# sleep-monitor.net
KiCad netlist of a schematic drawn in EasyEDA Pro
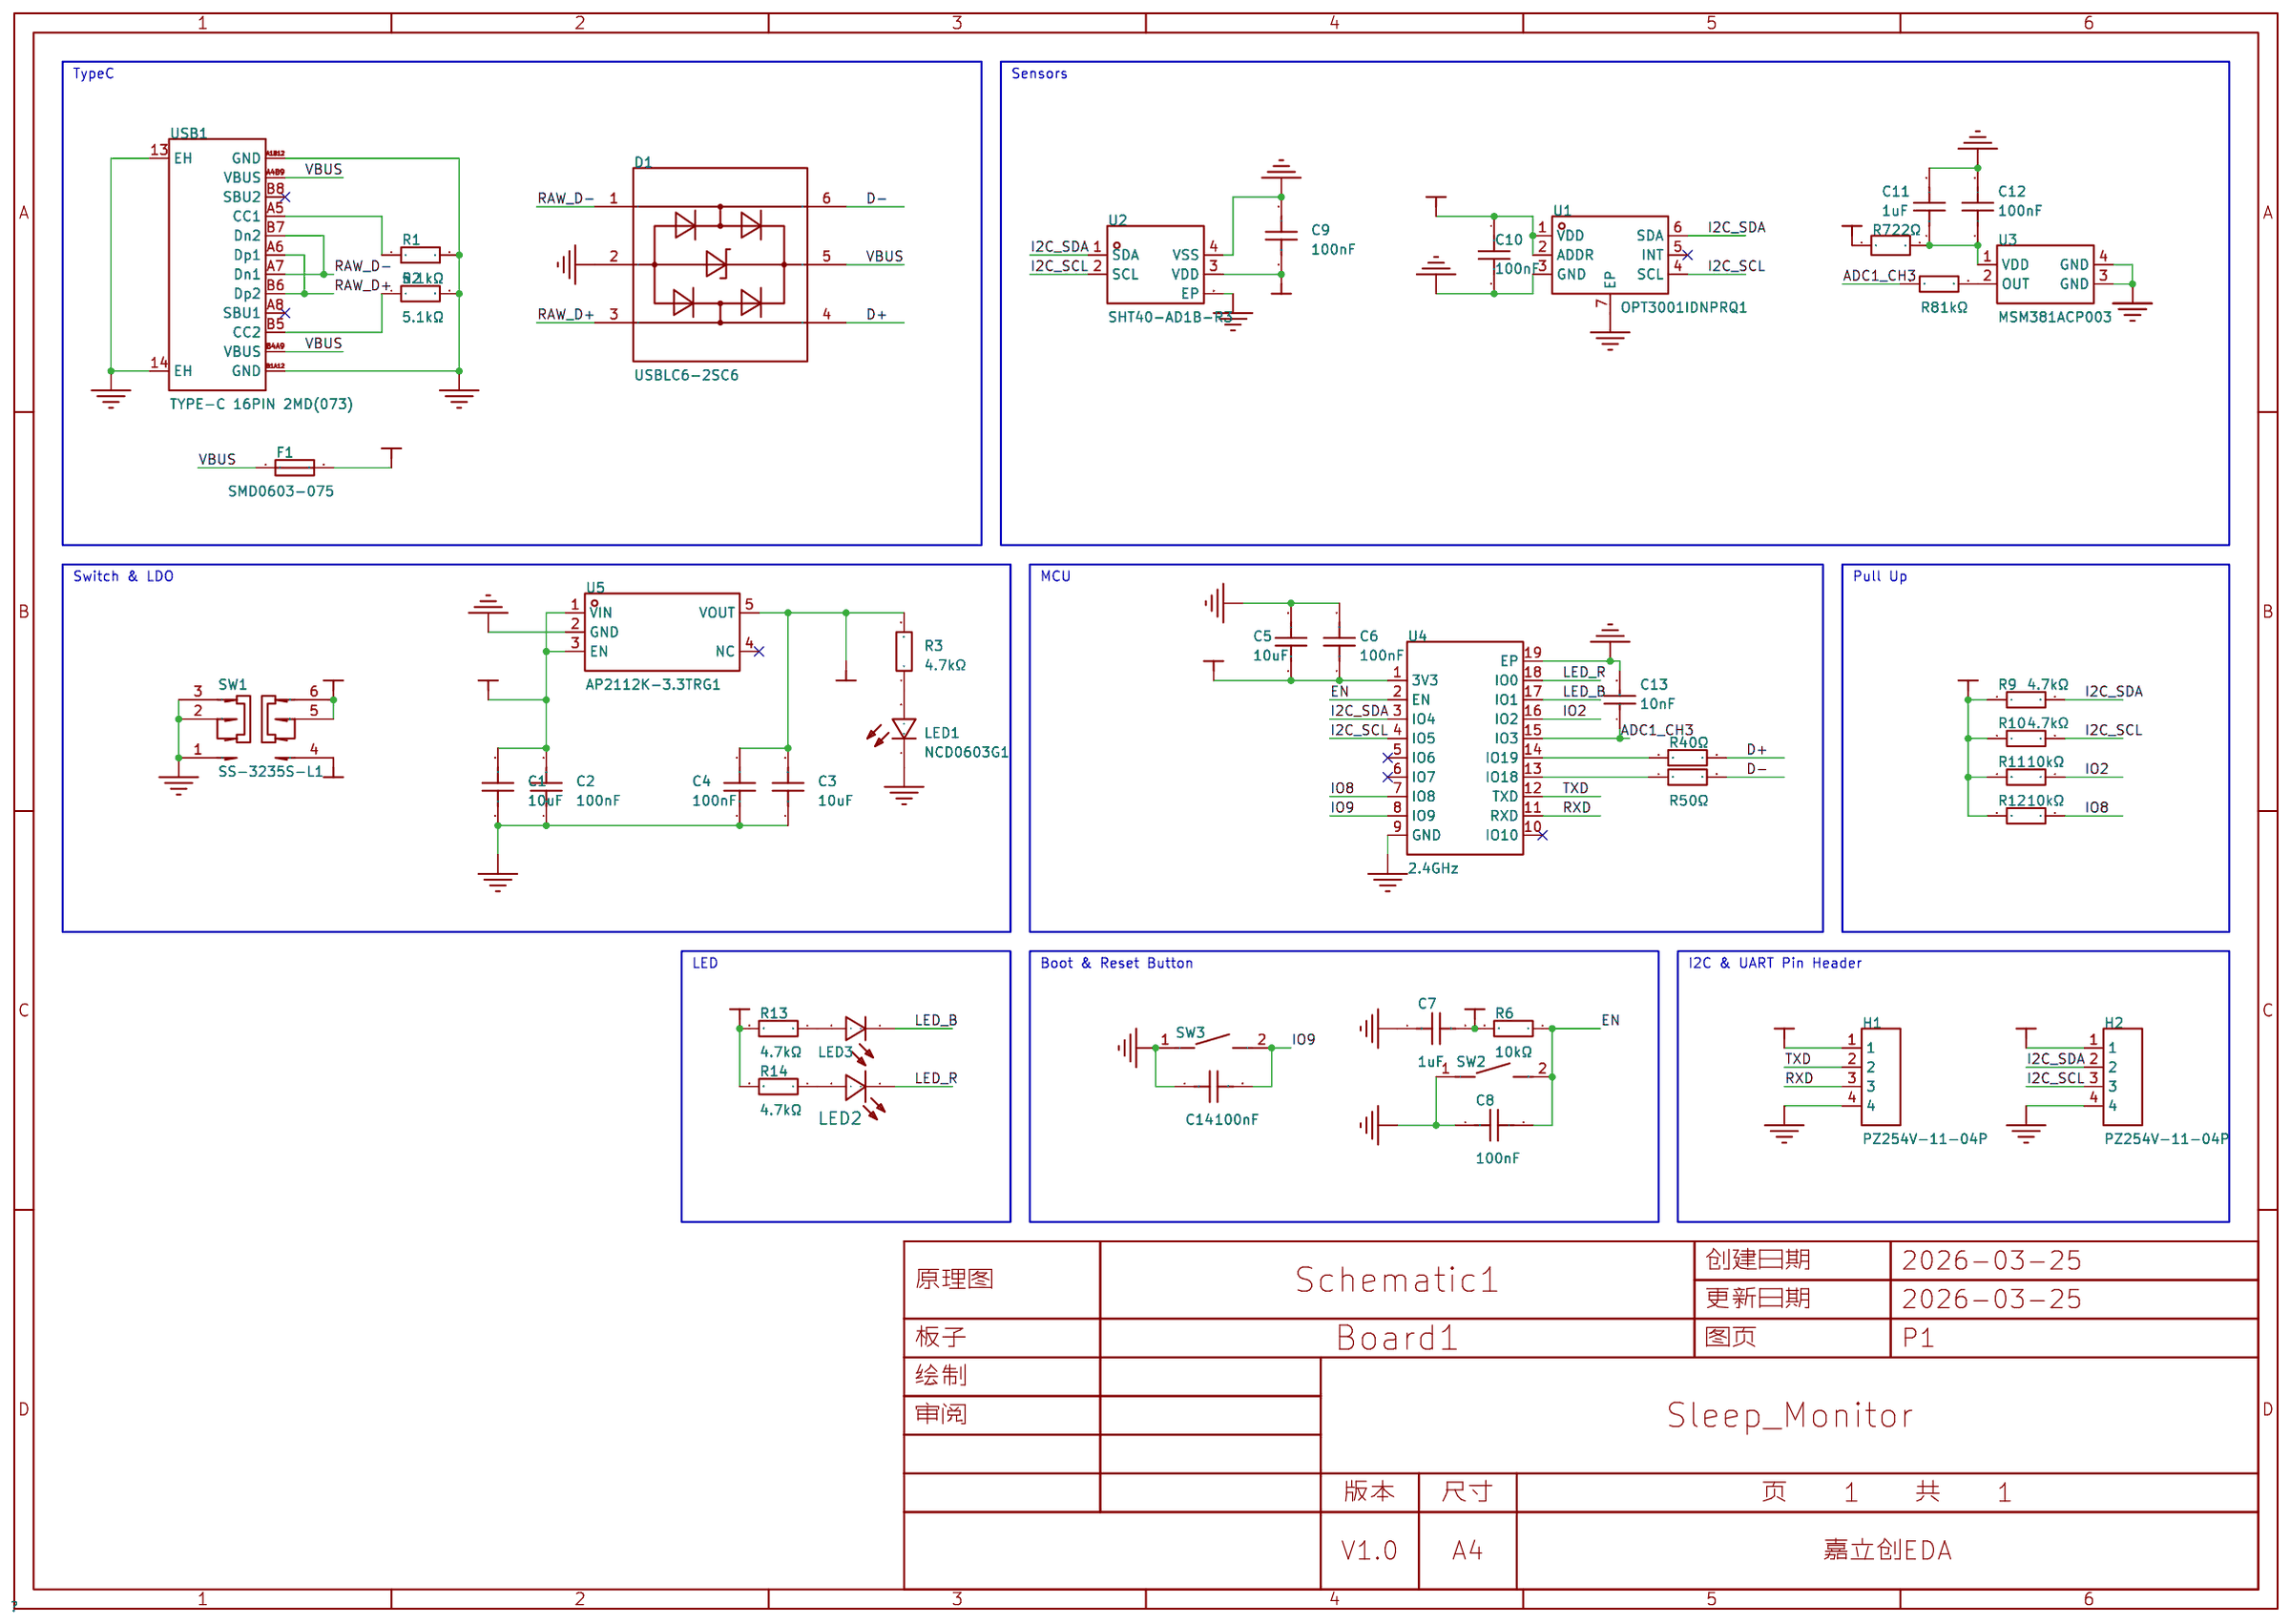
[diagram p0: schematic sheet]

(export (version "E")
  (design (tool "Eeschema 10.0.6"))
  (components
    (comp (ref "C1")
      (value "10uF")
      (footprint "easyedapro:C0603")
      (description "容值:10uF;精度:±10%;额定电压:10V;温度系数:X5R;")
      (fields
        (field (name "Manufacturer Part") "CL10A106KP8NNNC")
        (field (name "Manufacturer") "SAMSUNG(三星)")
      )
      (libsource (lib "easyedapro") (part "CL10A106KP8NNNC"))
    )
    (comp (ref "C2")
      (value "100nF")
      (footprint "easyedapro:C0603")
      (description "容值:100nF;精度:±10%;额定电压:50V;温度系数:X7R;")
      (fields
        (field (name "Manufacturer Part") "CL10B104KB8NNNC")
        (field (name "Manufacturer") "SAMSUNG(三星)")
      )
      (libsource (lib "easyedapro") (part "CL10B104KB8NNNC"))
    )
    (comp (ref "C3")
      (value "10uF")
      (footprint "easyedapro:C0603")
      (description "容值:10uF;精度:±10%;额定电压:10V;温度系数:X5R;")
      (fields
        (field (name "Manufacturer Part") "CL10A106KP8NNNC")
        (field (name "Manufacturer") "SAMSUNG(三星)")
      )
      (libsource (lib "easyedapro") (part "CL10A106KP8NNNC"))
    )
    (comp (ref "C4")
      (value "100nF")
      (footprint "easyedapro:C0603")
      (description "容值:100nF;精度:±10%;额定电压:50V;温度系数:X7R;")
      (fields
        (field (name "Manufacturer Part") "CL10B104KB8NNNC")
        (field (name "Manufacturer") "SAMSUNG(三星)")
      )
      (libsource (lib "easyedapro") (part "CL10B104KB8NNNC"))
    )
    (comp (ref "C5")
      (value "10uF")
      (footprint "easyedapro:C0603")
      (description "容值:10uF;精度:±10%;额定电压:10V;温度系数:X5R;")
      (fields
        (field (name "Manufacturer Part") "CL10A106KP8NNNC")
        (field (name "Manufacturer") "SAMSUNG(三星)")
      )
      (libsource (lib "easyedapro") (part "CL10A106KP8NNNC"))
    )
    (comp (ref "C6")
      (value "100nF")
      (footprint "easyedapro:C0603")
      (description "容值:100nF;精度:±10%;额定电压:50V;温度系数:X7R;")
      (fields
        (field (name "Manufacturer Part") "CL10B104KB8NNNC")
        (field (name "Manufacturer") "SAMSUNG(三星)")
      )
      (libsource (lib "easyedapro") (part "CL10B104KB8NNNC"))
    )
    (comp (ref "C7")
      (value "1uF")
      (footprint "easyedapro:C0603")
      (description "容值:1uF;精度:±10%;额定电压:50V;温度系数:X5R;")
      (fields
        (field (name "Manufacturer Part") "CL10A105KB8NNNC")
        (field (name "Manufacturer") "SAMSUNG(三星)")
      )
      (libsource (lib "easyedapro") (part "CL10A105KB8NNNC"))
    )
    (comp (ref "C8")
      (value "100nF")
      (footprint "easyedapro:C0603")
      (description "容值:100nF;精度:±10%;额定电压:50V;温度系数:X7R;")
      (fields
        (field (name "Manufacturer Part") "CL10B104KB8NNNC")
        (field (name "Manufacturer") "SAMSUNG(三星)")
      )
      (libsource (lib "easyedapro") (part "CL10B104KB8NNNC"))
    )
    (comp (ref "C9")
      (value "100nF")
      (footprint "easyedapro:C0603")
      (description "容值:100nF;精度:±10%;额定电压:50V;温度系数:X7R;")
      (fields
        (field (name "Manufacturer Part") "CL10B104KB8NNNC")
        (field (name "Manufacturer") "SAMSUNG(三星)")
      )
      (libsource (lib "easyedapro") (part "CL10B104KB8NNNC"))
    )
    (comp (ref "C10")
      (value "100nF")
      (footprint "easyedapro:C0603")
      (description "容值:100nF;精度:±10%;额定电压:50V;温度系数:X7R;")
      (fields
        (field (name "Manufacturer Part") "CL10B104KB8NNNC")
        (field (name "Manufacturer") "SAMSUNG(三星)")
      )
      (libsource (lib "easyedapro") (part "CL10B104KB8NNNC"))
    )
    (comp (ref "C11")
      (value "1uF")
      (footprint "easyedapro:C0603")
      (description "容值:1uF;精度:±10%;额定电压:50V;温度系数:X5R;")
      (fields
        (field (name "Manufacturer Part") "CL10A105KB8NNNC")
        (field (name "Manufacturer") "SAMSUNG(三星)")
      )
      (libsource (lib "easyedapro") (part "CL10A105KB8NNNC"))
    )
    (comp (ref "C12")
      (value "100nF")
      (footprint "easyedapro:C0603")
      (description "容值:100nF;精度:±10%;额定电压:50V;温度系数:X7R;")
      (fields
        (field (name "Manufacturer Part") "CL10B104KB8NNNC")
        (field (name "Manufacturer") "SAMSUNG(三星)")
      )
      (libsource (lib "easyedapro") (part "CL10B104KB8NNNC"))
    )
    (comp (ref "C13")
      (value "10nF")
      (footprint "easyedapro:C0603")
      (description "容值:10nF;精度:±10%;额定电压:50V;温度系数:X7R;")
      (fields (field (name "Manufacturer Part") "0603B103K500NT") (field (name "Manufacturer") "FH(风华)"))
      (libsource (lib "easyedapro") (part "0603B103K500NT"))
    )
    (comp (ref "C14")
      (value "100nF")
      (footprint "easyedapro:C0603")
      (description "容值:100nF;精度:±10%;额定电压:50V;温度系数:X7R;")
      (fields
        (field (name "Manufacturer Part") "CL10B104KB8NNNC")
        (field (name "Manufacturer") "SAMSUNG(三星)")
      )
      (libsource (lib "easyedapro") (part "CL10B104KB8NNNC"))
    )
    (comp (ref "D1")
      (value "USBLC6-2SC6")
      (footprint "easyedapro:SOT-23-6_L2.9-W1.6-P0.95-LS2.8-BL")
      (fields (field (name "Manufacturer") "ST(意法半导体)"))
      (libsource (lib "easyedapro") (part "USBLC6-2SC6"))
    )
    (comp (ref "F1")
      (value "SMD0603-075")
      (footprint "easyedapro:F0603")
      (fields (field (name "Manufacturer") "台湾陆海"))
      (libsource (lib "easyedapro") (part "0603-075"))
    )
    (comp (ref "H1")
      (value "PZ254V-11-04P")
      (footprint "easyedapro:HDR-TH_4P-P2.54-V-M")
      (fields (field (name "Manufacturer") "XFCN(兴飞)"))
      (libsource (lib "easyedapro") (part "PZ254V-11-04P"))
    )
    (comp (ref "H2")
      (value "PZ254V-11-04P")
      (footprint "easyedapro:HDR-TH_4P-P2.54-V-M")
      (fields (field (name "Manufacturer") "XFCN(兴飞)"))
      (libsource (lib "easyedapro") (part "PZ254V-11-04P"))
    )
    (comp (ref "LED1")
      (value "NCD0603G1")
      (footprint "easyedapro:LED0603-RD_1")
      (fields (field (name "Manufacturer") "国星光电"))
      (libsource (lib "easyedapro") (part "FC-D1608UGK-520D10"))
    )
    (comp (ref "LED2")
      (value "NCD0603R5")
      (footprint "easyedapro:LED0603-RD")
      (fields (field (name "Manufacturer") "国星光电"))
      (libsource (lib "easyedapro") (part "NCD0603R5"))
    )
    (comp (ref "LED3")
      (value "NCD0603B1")
      (footprint "easyedapro:LED0603-RD")
      (fields (field (name "Manufacturer") "国星光电"))
      (libsource (lib "easyedapro") (part "FC-DA1608BK-470H10"))
    )
    (comp (ref "R1")
      (value "5.1kΩ")
      (footprint "easyedapro:R0603")
      (description "电阻类型:厚膜电阻;阻值:5.1kΩ;精度:±1%;功率:100mW;工作电压:75V;温度系数:±100ppm/℃;")
      (fields
        (field (name "Manufacturer Part") "0603WAF5101T5E")
        (field (name "Manufacturer") "UNI-ROYAL(厚声)")
      )
      (libsource (lib "easyedapro") (part "0603WAF5101T5E"))
    )
    (comp (ref "R2")
      (value "5.1kΩ")
      (footprint "easyedapro:R0603")
      (description "电阻类型:厚膜电阻;阻值:5.1kΩ;精度:±1%;功率:100mW;工作电压:75V;温度系数:±100ppm/℃;")
      (fields
        (field (name "Manufacturer Part") "0603WAF5101T5E")
        (field (name "Manufacturer") "UNI-ROYAL(厚声)")
      )
      (libsource (lib "easyedapro") (part "0603WAF5101T5E"))
    )
    (comp (ref "R3")
      (value "4.7kΩ")
      (footprint "easyedapro:R0603")
      (description "电阻类型:厚膜电阻;阻值:4.7kΩ;精度:±1%;功率:100mW;工作电压:75V;温度系数:±100ppm/℃;")
      (fields
        (field (name "Manufacturer Part") "0603WAF4701T5E")
        (field (name "Manufacturer") "UNI-ROYAL(厚声)")
      )
      (libsource (lib "easyedapro") (part "0603WAF4701T5E"))
    )
    (comp (ref "R4")
      (value "0Ω")
      (footprint "easyedapro:R0603")
      (description "电阻类型:厚膜电阻;阻值:0Ω;精度:±1%;功率:100mW;工作电压:75V;温度系数:-;")
      (fields
        (field (name "Manufacturer Part") "0603WAF0000T5E")
        (field (name "Manufacturer") "UNI-ROYAL(厚声)")
      )
      (libsource (lib "easyedapro") (part "0603WAF0000T5E"))
    )
    (comp (ref "R5")
      (value "0Ω")
      (footprint "easyedapro:R0603")
      (description "电阻类型:厚膜电阻;阻值:0Ω;精度:±1%;功率:100mW;工作电压:75V;温度系数:-;")
      (fields
        (field (name "Manufacturer Part") "0603WAF0000T5E")
        (field (name "Manufacturer") "UNI-ROYAL(厚声)")
      )
      (libsource (lib "easyedapro") (part "0603WAF0000T5E"))
    )
    (comp (ref "R6")
      (value "10kΩ")
      (footprint "easyedapro:R0603")
      (description "电阻类型:厚膜电阻;阻值:10kΩ;精度:±1%;功率:100mW;工作电压:75V;温度系数:±100ppm/℃;")
      (fields
        (field (name "Manufacturer Part") "0603WAF1002T5E")
        (field (name "Manufacturer") "UNI-ROYAL(厚声)")
      )
      (libsource (lib "easyedapro") (part "0603WAF1002T5E"))
    )
    (comp (ref "R7")
      (value "22Ω")
      (footprint "easyedapro:R0603")
      (description "电阻类型:厚膜电阻;阻值:22Ω;精度:±1%;功率:100mW;工作电压:75V;温度系数:±100ppm/℃;")
      (fields (field (name "Manufacturer Part") "FRC0603F22R0TS") (field (name "Manufacturer") "FOJAN(富捷)"))
      (libsource (lib "easyedapro") (part "FRC0603F22R0TS"))
    )
    (comp (ref "R8")
      (value "1kΩ")
      (footprint "easyedapro:R0603")
      (description "电阻类型:厚膜电阻;阻值:1kΩ;精度:±1%;功率:100mW;工作电压:75V;温度系数:±100ppm/℃;")
      (fields
        (field (name "Manufacturer Part") "0603WAF1001T5E")
        (field (name "Manufacturer") "UNI-ROYAL(厚声)")
      )
      (libsource (lib "easyedapro") (part "0603WAF1001T5E"))
    )
    (comp (ref "R9")
      (value "4.7kΩ")
      (footprint "easyedapro:R0603")
      (description "电阻类型:厚膜电阻;阻值:4.7kΩ;精度:±1%;功率:100mW;工作电压:75V;温度系数:±100ppm/℃;")
      (fields
        (field (name "Manufacturer Part") "0603WAF4701T5E")
        (field (name "Manufacturer") "UNI-ROYAL(厚声)")
      )
      (libsource (lib "easyedapro") (part "0603WAF4701T5E"))
    )
    (comp (ref "R10")
      (value "4.7kΩ")
      (footprint "easyedapro:R0603")
      (description "电阻类型:厚膜电阻;阻值:4.7kΩ;精度:±1%;功率:100mW;工作电压:75V;温度系数:±100ppm/℃;")
      (fields
        (field (name "Manufacturer Part") "0603WAF4701T5E")
        (field (name "Manufacturer") "UNI-ROYAL(厚声)")
      )
      (libsource (lib "easyedapro") (part "0603WAF4701T5E"))
    )
    (comp (ref "R11")
      (value "10kΩ")
      (footprint "easyedapro:R0603")
      (description "电阻类型:厚膜电阻;阻值:10kΩ;精度:±1%;功率:100mW;工作电压:75V;温度系数:±100ppm/℃;")
      (fields
        (field (name "Manufacturer Part") "0603WAF1002T5E")
        (field (name "Manufacturer") "UNI-ROYAL(厚声)")
      )
      (libsource (lib "easyedapro") (part "0603WAF1002T5E"))
    )
    (comp (ref "R12")
      (value "10kΩ")
      (footprint "easyedapro:R0603")
      (description "电阻类型:厚膜电阻;阻值:10kΩ;精度:±1%;功率:100mW;工作电压:75V;温度系数:±100ppm/℃;")
      (fields
        (field (name "Manufacturer Part") "0603WAF1002T5E")
        (field (name "Manufacturer") "UNI-ROYAL(厚声)")
      )
      (libsource (lib "easyedapro") (part "0603WAF1002T5E"))
    )
    (comp (ref "R13")
      (value "4.7kΩ")
      (footprint "easyedapro:R0603")
      (description "电阻类型:厚膜电阻;阻值:4.7kΩ;精度:±1%;功率:100mW;工作电压:75V;温度系数:±100ppm/℃;")
      (fields
        (field (name "Manufacturer Part") "0603WAF4701T5E")
        (field (name "Manufacturer") "UNI-ROYAL(厚声)")
      )
      (libsource (lib "easyedapro") (part "0603WAF4701T5E"))
    )
    (comp (ref "R14")
      (value "4.7kΩ")
      (footprint "easyedapro:R0603")
      (description "电阻类型:厚膜电阻;阻值:4.7kΩ;精度:±1%;功率:100mW;工作电压:75V;温度系数:±100ppm/℃;")
      (fields
        (field (name "Manufacturer Part") "0603WAF4701T5E")
        (field (name "Manufacturer") "UNI-ROYAL(厚声)")
      )
      (libsource (lib "easyedapro") (part "0603WAF4701T5E"))
    )
    (comp (ref "SW1")
      (value "SS-3235S-L1")
      (footprint "easyedapro:SW-SMD_SS-3235S-LX")
      (fields (field (name "Manufacturer") "XKB Connection(中国星坤)"))
      (libsource (lib "easyedapro") (part "SS-3235S-L1"))
    )
    (comp (ref "SW2")
      (value "TS-1088-AR02016")
      (footprint "easyedapro:SW-SMD_L3.9-W3.0-P4.45")
      (fields (field (name "Manufacturer") "XUNPU(讯普)"))
      (libsource (lib "easyedapro") (part "TS-1088-AR02016"))
    )
    (comp (ref "SW3")
      (value "TS-1088-AR02016")
      (footprint "easyedapro:SW-SMD_L3.9-W3.0-P4.45")
      (fields (field (name "Manufacturer") "XUNPU(讯普)"))
      (libsource (lib "easyedapro") (part "TS-1088-AR02016"))
    )
    (comp (ref "U1")
      (value "OPT3001IDNPRQ1")
      (footprint "easyedapro:WSON-6_L2.0-W2.0-P0.65-BL-EP")
      (description "OPT3001-Q1 具有高精度人眼响应功能的汽车数字环境光传感器 (ALS)")
      (fields (field (name "Manufacturer") "TI(德州仪器)"))
      (libsource (lib "easyedapro") (part "OPT3001IDNPRQ1"))
    )
    (comp (ref "U2")
      (value "SHT40-AD1B-R3")
      (footprint "easyedapro:DFN-4_L1.5-W1.5-P0.8-TL-EP")
      (description "温度范围:-40℃~+125℃;湿度范围:0%RH~100%RH;接口类型:I2C;湿度精度:±1.8%RH;")
      (fields (field (name "Manufacturer") "Sensirion(瑞士盛思锐)"))
      (libsource (lib "easyedapro") (part "SHT40-AD1B-R3"))
    )
    (comp (ref "U3")
      (value "MSM381ACP003")
      (footprint "easyedapro:MIC-SMD_4P-L2.8-W1.9-TR_MSM381ACP003")
      (description "指向性:全指向型;信噪比:64dB;灵敏度:-38dB;阻抗:170Ω;")
      (fields (field (name "Manufacturer") "MEMS(敏芯微)"))
      (libsource (lib "easyedapro") (part "MSM381ACP003_C51928212"))
    )
    (comp (ref "U4")
      (value "2.4GHz")
      (footprint "easyedapro:BULETM-SMD_ESPRESSIF_ESP32-C3-WROOM-02-N4-4MB")
      (fields
        (field (name "Manufacturer Part") "ESP32-C3-WROOM-02-N4")
        (field (name "Manufacturer") "ESPRESSIF(乐鑫)")
      )
      (libsource (lib "easyedapro") (part "ESP32-C3-WROOM-02-N4(4MB)"))
    )
    (comp (ref "U5")
      (value "AP2112K-3.3TRG1")
      (footprint "easyedapro:SOT-25-5_L2.9-W1.6-P0.95-LS2.8-BL")
      (fields (field (name "Manufacturer") "DIODES(美台)"))
      (libsource (lib "easyedapro") (part "AP2112K-3.3TRG1"))
    )
    (comp (ref "USB1")
      (value "TYPE-C 16PIN 2MD(073)")
      (footprint "easyedapro:USB-C-SMD_TYPE-C-16PIN-2MD-073")
      (fields (field (name "Manufacturer") "SHOU HAN(首韩)"))
      (libsource (lib "easyedapro") (part "TYPE-C 16PIN 2MD(073)"))
    )
  )
  (nets
    (net (code "1") (name "+3.3V") (class "Default")
      (node (ref "C10") (pin "1") (pinfunction "1_1") (pintype "unspecified"))
      (node (ref "C3") (pin "2") (pinfunction "2_2") (pintype "unspecified"))
      (node (ref "C4") (pin "2") (pinfunction "2_2") (pintype "unspecified"))
      (node (ref "C5") (pin "1") (pinfunction "1_1") (pintype "unspecified"))
      (node (ref "C6") (pin "1") (pinfunction "1_1") (pintype "unspecified"))
      (node (ref "C7") (pin "2") (pinfunction "2_2") (pintype "unspecified"))
      (node (ref "C9") (pin "2") (pinfunction "2_2") (pintype "unspecified"))
      (node (ref "H1") (pin "1") (pinfunction "1_1") (pintype "unspecified"))
      (node (ref "H2") (pin "1") (pinfunction "1_1") (pintype "unspecified"))
      (node (ref "R10") (pin "1") (pinfunction "1_1") (pintype "input"))
      (node (ref "R11") (pin "2") (pinfunction "2_2") (pintype "input"))
      (node (ref "R12") (pin "2") (pinfunction "2_2") (pintype "input"))
      (node (ref "R13") (pin "2") (pinfunction "2_2") (pintype "input"))
      (node (ref "R14") (pin "2") (pinfunction "2_2") (pintype "input"))
      (node (ref "R3") (pin "2") (pinfunction "2_2") (pintype "input"))
      (node (ref "R6") (pin "2") (pinfunction "2_2") (pintype "input"))
      (node (ref "R7") (pin "1") (pinfunction "1_1") (pintype "unspecified"))
      (node (ref "R9") (pin "1") (pinfunction "1_1") (pintype "input"))
      (node (ref "U1") (pin "1") (pinfunction "VDD_1") (pintype "unspecified"))
      (node (ref "U1") (pin "2") (pinfunction "ADDR_2") (pintype "unspecified"))
      (node (ref "U2") (pin "3") (pinfunction "VDD_3") (pintype "unspecified"))
      (node (ref "U4") (pin "1") (pinfunction "3V3_1") (pintype "unspecified"))
      (node (ref "U5") (pin "5") (pinfunction "VOUT_5") (pintype "unspecified"))
    )
    (net (code "2") (name "+5V") (class "Default")
      (node (ref "C1") (pin "2") (pinfunction "2_2") (pintype "unspecified"))
      (node (ref "C2") (pin "2") (pinfunction "2_2") (pintype "unspecified"))
      (node (ref "SW1") (pin "5") (pinfunction "5_5") (pintype "unspecified"))
      (node (ref "SW1") (pin "6") (pinfunction "6_6") (pintype "unspecified"))
      (node (ref "U5") (pin "1") (pinfunction "VIN_1") (pintype "unspecified"))
      (node (ref "U5") (pin "3") (pinfunction "EN_3") (pintype "unspecified"))
    )
    (net (code "3") (name "/ADC1_CH3") (class "Default")
      (node (ref "C13") (pin "1") (pinfunction "1_1") (pintype "input"))
      (node (ref "R8") (pin "1") (pinfunction "1_1") (pintype "input"))
      (node (ref "U4") (pin "15") (pinfunction "IO3_15") (pintype "unspecified"))
    )
    (net (code "4") (name "/D+") (class "Default")
      (node (ref "D1") (pin "4") (pinfunction "4_4") (pintype "input"))
      (node (ref "R4") (pin "2") (pinfunction "2_2") (pintype "input"))
    )
    (net (code "5") (name "/D-") (class "Default")
      (node (ref "D1") (pin "6") (pinfunction "6_6") (pintype "input"))
      (node (ref "R5") (pin "2") (pinfunction "2_2") (pintype "input"))
    )
    (net (code "6") (name "/EN") (class "Default")
      (node (ref "C8") (pin "2") (pinfunction "2_2") (pintype "unspecified"))
      (node (ref "R6") (pin "1") (pinfunction "1_1") (pintype "input"))
      (node (ref "SW2") (pin "2") (pinfunction "2_2") (pintype "unspecified"))
      (node (ref "U4") (pin "2") (pinfunction "EN_2") (pintype "unspecified"))
    )
    (net (code "7") (name "/I2C_SCL") (class "Default")
      (node (ref "H2") (pin "3") (pinfunction "3_3") (pintype "unspecified"))
      (node (ref "R10") (pin "2") (pinfunction "2_2") (pintype "input"))
      (node (ref "U1") (pin "4") (pinfunction "SCL_4") (pintype "unspecified"))
      (node (ref "U2") (pin "2") (pinfunction "SCL_2") (pintype "unspecified"))
      (node (ref "U4") (pin "4") (pinfunction "IO5_4") (pintype "unspecified"))
    )
    (net (code "8") (name "/I2C_SDA") (class "Default")
      (node (ref "H2") (pin "2") (pinfunction "2_2") (pintype "unspecified"))
      (node (ref "R9") (pin "2") (pinfunction "2_2") (pintype "input"))
      (node (ref "U1") (pin "6") (pinfunction "SDA_6") (pintype "unspecified"))
      (node (ref "U2") (pin "1") (pinfunction "SDA_1") (pintype "unspecified"))
      (node (ref "U4") (pin "3") (pinfunction "IO4_3") (pintype "unspecified"))
    )
    (net (code "9") (name "/IO2") (class "Default")
      (node (ref "R11") (pin "1") (pinfunction "1_1") (pintype "input"))
      (node (ref "U4") (pin "16") (pinfunction "IO2_16") (pintype "unspecified"))
    )
    (net (code "10") (name "/IO8") (class "Default")
      (node (ref "R12") (pin "1") (pinfunction "1_1") (pintype "input"))
      (node (ref "U4") (pin "7") (pinfunction "IO8_7") (pintype "unspecified"))
    )
    (net (code "11") (name "/IO9") (class "Default")
      (node (ref "C14") (pin "2") (pinfunction "2_2") (pintype "unspecified"))
      (node (ref "SW3") (pin "2") (pinfunction "2_2") (pintype "unspecified"))
      (node (ref "U4") (pin "8") (pinfunction "IO9_8") (pintype "unspecified"))
    )
    (net (code "12") (name "/LED_B") (class "Default")
      (node (ref "LED3") (pin "1") (pinfunction "-_1") (pintype "input"))
      (node (ref "U4") (pin "17") (pinfunction "IO1_17") (pintype "unspecified"))
    )
    (net (code "13") (name "/LED_R") (class "Default")
      (node (ref "LED2") (pin "1") (pinfunction "-_1") (pintype "unspecified"))
      (node (ref "U4") (pin "18") (pinfunction "IO0_18") (pintype "unspecified"))
    )
    (net (code "14") (name "/RAW_D+") (class "Default")
      (node (ref "D1") (pin "3") (pinfunction "3_3") (pintype "input"))
      (node (ref "USB1") (pin "A6") (pinfunction "Dp1_A6") (pintype "unspecified"))
      (node (ref "USB1") (pin "B6") (pinfunction "Dp2_B6") (pintype "unspecified"))
    )
    (net (code "15") (name "/RAW_D-") (class "Default")
      (node (ref "D1") (pin "1") (pinfunction "1_1") (pintype "input"))
      (node (ref "USB1") (pin "A7") (pinfunction "Dn1_A7") (pintype "unspecified"))
      (node (ref "USB1") (pin "B7") (pinfunction "Dn2_B7") (pintype "unspecified"))
    )
    (net (code "16") (name "/RXD") (class "Default")
      (node (ref "H1") (pin "3") (pinfunction "3_3") (pintype "unspecified"))
      (node (ref "U4") (pin "11") (pinfunction "RXD_11") (pintype "unspecified"))
    )
    (net (code "17") (name "/TXD") (class "Default")
      (node (ref "H1") (pin "2") (pinfunction "2_2") (pintype "unspecified"))
      (node (ref "U4") (pin "12") (pinfunction "TXD_12") (pintype "unspecified"))
    )
    (net (code "18") (name "/VBUS") (class "Default")
      (node (ref "D1") (pin "5") (pinfunction "5_5") (pintype "input"))
      (node (ref "F1") (pin "1") (pinfunction "1_1") (pintype "unspecified"))
      (node (ref "USB1") (pin "A4B9") (pinfunction "VBUS_A4B9") (pintype "unspecified"))
      (node (ref "USB1") (pin "B4A9") (pinfunction "VBUS_B4A9") (pintype "unspecified"))
    )
    (net (code "19") (name "GND") (class "Default")
      (node (ref "C1") (pin "1") (pinfunction "1_1") (pintype "unspecified"))
      (node (ref "C10") (pin "2") (pinfunction "2_2") (pintype "unspecified"))
      (node (ref "C11") (pin "2") (pinfunction "2_2") (pintype "unspecified"))
      (node (ref "C12") (pin "2") (pinfunction "2_2") (pintype "unspecified"))
      (node (ref "C13") (pin "2") (pinfunction "2_2") (pintype "input"))
      (node (ref "C14") (pin "1") (pinfunction "1_1") (pintype "unspecified"))
      (node (ref "C2") (pin "1") (pinfunction "1_1") (pintype "unspecified"))
      (node (ref "C3") (pin "1") (pinfunction "1_1") (pintype "unspecified"))
      (node (ref "C4") (pin "1") (pinfunction "1_1") (pintype "unspecified"))
      (node (ref "C5") (pin "2") (pinfunction "2_2") (pintype "unspecified"))
      (node (ref "C6") (pin "2") (pinfunction "2_2") (pintype "unspecified"))
      (node (ref "C7") (pin "1") (pinfunction "1_1") (pintype "unspecified"))
      (node (ref "C8") (pin "1") (pinfunction "1_1") (pintype "unspecified"))
      (node (ref "C9") (pin "1") (pinfunction "1_1") (pintype "unspecified"))
      (node (ref "D1") (pin "2") (pinfunction "2_2") (pintype "input"))
      (node (ref "H1") (pin "4") (pinfunction "4_4") (pintype "unspecified"))
      (node (ref "H2") (pin "4") (pinfunction "4_4") (pintype "unspecified"))
      (node (ref "LED1") (pin "1") (pinfunction "K_1") (pintype "input"))
      (node (ref "R1") (pin "2") (pinfunction "2_2") (pintype "input"))
      (node (ref "R2") (pin "2") (pinfunction "2_2") (pintype "input"))
      (node (ref "SW1") (pin "1") (pinfunction "1_1") (pintype "unspecified"))
      (node (ref "SW1") (pin "2") (pinfunction "2_2") (pintype "unspecified"))
      (node (ref "SW1") (pin "3") (pinfunction "3_3") (pintype "unspecified"))
      (node (ref "SW2") (pin "1") (pinfunction "1_1") (pintype "unspecified"))
      (node (ref "SW3") (pin "1") (pinfunction "1_1") (pintype "unspecified"))
      (node (ref "U1") (pin "3") (pinfunction "GND_3") (pintype "unspecified"))
      (node (ref "U1") (pin "7") (pinfunction "EP_7") (pintype "unspecified"))
      (node (ref "U2") (pin "4") (pinfunction "VSS_4") (pintype "unspecified"))
      (node (ref "U2") (pin "5") (pinfunction "EP_5") (pintype "unspecified"))
      (node (ref "U3") (pin "3") (pinfunction "GND_3") (pintype "unspecified"))
      (node (ref "U3") (pin "4") (pinfunction "GND_4") (pintype "unspecified"))
      (node (ref "U4") (pin "19") (pinfunction "EP_19") (pintype "unspecified"))
      (node (ref "U4") (pin "9") (pinfunction "GND_9") (pintype "unspecified"))
      (node (ref "U5") (pin "2") (pinfunction "GND_2") (pintype "unspecified"))
      (node (ref "USB1") (pin "13") (pinfunction "EH_13") (pintype "unspecified"))
      (node (ref "USB1") (pin "14") (pinfunction "EH_14") (pintype "unspecified"))
      (node (ref "USB1") (pin "A1B12") (pinfunction "GND_A1B12") (pintype "unspecified"))
      (node (ref "USB1") (pin "B1A12") (pinfunction "GND_B1A12") (pintype "unspecified"))
    )
    (net (code "20") (name "Net-(LED1-A)") (class "Default")
      (node (ref "LED1") (pin "2") (pinfunction "A_2") (pintype "input"))
      (node (ref "R3") (pin "1") (pinfunction "1_1") (pintype "input"))
    )
    (net (code "21") (name "Net-(LED2-+)") (class "Default")
      (node (ref "LED2") (pin "2") (pinfunction "+_2") (pintype "unspecified"))
      (node (ref "R14") (pin "1") (pinfunction "1_1") (pintype "input"))
    )
    (net (code "22") (name "Net-(LED3-+)") (class "Default")
      (node (ref "LED3") (pin "2") (pinfunction "+_2") (pintype "input"))
      (node (ref "R13") (pin "1") (pinfunction "1_1") (pintype "input"))
    )
    (net (code "23") (name "Net-(U3-OUT)") (class "Default")
      (node (ref "R8") (pin "2") (pinfunction "2_2") (pintype "input"))
      (node (ref "U3") (pin "2") (pinfunction "OUT_2") (pintype "unspecified"))
    )
    (net (code "24") (name "Net-(U3-VDD)") (class "Default")
      (node (ref "C11") (pin "1") (pinfunction "1_1") (pintype "unspecified"))
      (node (ref "C12") (pin "1") (pinfunction "1_1") (pintype "unspecified"))
      (node (ref "R7") (pin "2") (pinfunction "2_2") (pintype "unspecified"))
      (node (ref "U3") (pin "1") (pinfunction "VDD_1") (pintype "unspecified"))
    )
    (net (code "25") (name "Net-(U4-IO18)") (class "Default")
      (node (ref "R5") (pin "1") (pinfunction "1_1") (pintype "input"))
      (node (ref "U4") (pin "13") (pinfunction "IO18_13") (pintype "unspecified"))
    )
    (net (code "26") (name "Net-(U4-IO19)") (class "Default")
      (node (ref "R4") (pin "1") (pinfunction "1_1") (pintype "input"))
      (node (ref "U4") (pin "14") (pinfunction "IO19_14") (pintype "unspecified"))
    )
    (net (code "27") (name "Net-(USB1-CC1)") (class "Default")
      (node (ref "R1") (pin "1") (pinfunction "1_1") (pintype "input"))
      (node (ref "USB1") (pin "A5") (pinfunction "CC1_A5") (pintype "unspecified"))
    )
    (net (code "28") (name "Net-(USB1-CC2)") (class "Default")
      (node (ref "R2") (pin "1") (pinfunction "1_1") (pintype "input"))
      (node (ref "USB1") (pin "B5") (pinfunction "CC2_B5") (pintype "unspecified"))
    )
    (net (code "29") (name "VCC+5V") (class "Default")
      (node (ref "F1") (pin "2") (pinfunction "2_2") (pintype "unspecified"))
      (node (ref "SW1") (pin "4") (pinfunction "4_4") (pintype "unspecified"))
    )
    (net (code "30") (name "unconnected-(U1-INT-Pad5)") (class "Default")
      (node (ref "U1") (pin "5") (pinfunction "INT_5") (pintype "unspecified+no_connect"))
    )
    (net (code "31") (name "unconnected-(U4-IO6-Pad5)") (class "Default")
      (node (ref "U4") (pin "5") (pinfunction "IO6_5") (pintype "unspecified+no_connect"))
    )
    (net (code "32") (name "unconnected-(U4-IO7-Pad6)") (class "Default")
      (node (ref "U4") (pin "6") (pinfunction "IO7_6") (pintype "unspecified+no_connect"))
    )
    (net (code "33") (name "unconnected-(U4-IO10-Pad10)") (class "Default")
      (node (ref "U4") (pin "10") (pinfunction "IO10_10") (pintype "unspecified+no_connect"))
    )
    (net (code "34") (name "unconnected-(U5-NC-Pad4)") (class "Default")
      (node (ref "U5") (pin "4") (pinfunction "NC_4") (pintype "unspecified+no_connect"))
    )
    (net (code "35") (name "unconnected-(USB1-SBU1-PadA8)") (class "Default")
      (node (ref "USB1") (pin "A8") (pinfunction "SBU1_A8") (pintype "unspecified+no_connect"))
    )
    (net (code "36") (name "unconnected-(USB1-SBU2-PadB8)") (class "Default")
      (node (ref "USB1") (pin "B8") (pinfunction "SBU2_B8") (pintype "unspecified+no_connect"))
    )
  )
)
